# rfid_v1.net
KiCad netlist of a schematic drawn in EAGLE
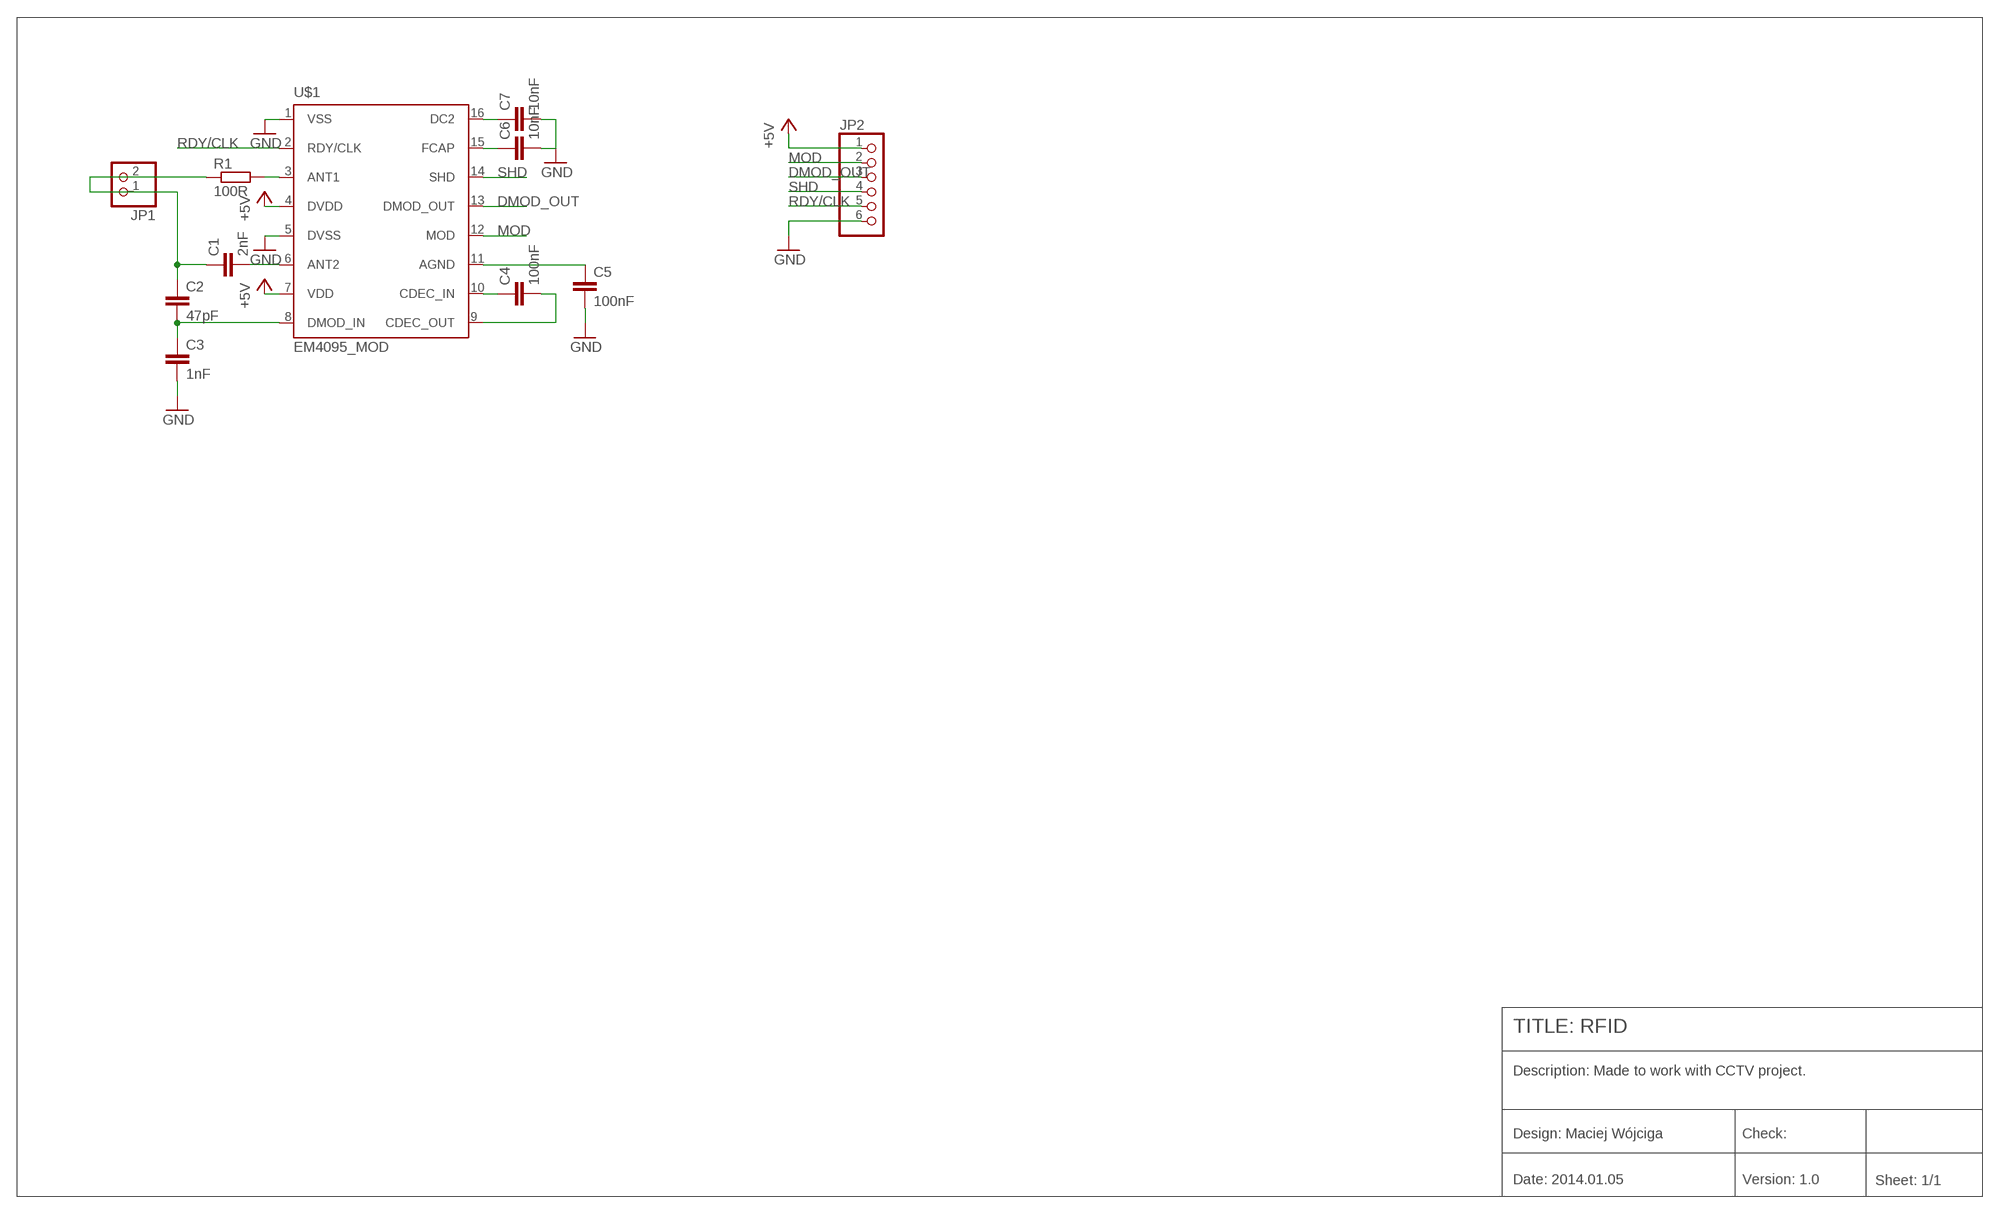
[diagram p0: schematic, sheet 1]

(export (version "E")
  (design (tool "Eeschema 10.0.6"))
  (components
    (comp (ref "C1")
      (value "2nF")
      (footprint "eagle-import:C025-024X044")
      (libsource (lib "eagle-import") (part "C-EU025-024X044"))
    )
    (comp (ref "C2")
      (value "47pF")
      (footprint "eagle-import:C025-024X044")
      (libsource (lib "eagle-import") (part "C-EU025-024X044"))
    )
    (comp (ref "C3")
      (value "1nF")
      (footprint "eagle-import:C025-024X044")
      (libsource (lib "eagle-import") (part "C-EU025-024X044"))
    )
    (comp (ref "C4")
      (value "100nF")
      (footprint "eagle-import:C025-024X044")
      (libsource (lib "eagle-import") (part "C-EU025-024X044"))
    )
    (comp (ref "C5")
      (value "100nF")
      (footprint "eagle-import:C025-024X044")
      (libsource (lib "eagle-import") (part "C-EU025-024X044"))
    )
    (comp (ref "C6")
      (value "10nF")
      (footprint "eagle-import:C025-024X044")
      (libsource (lib "eagle-import") (part "C-EU025-024X044"))
    )
    (comp (ref "C7")
      (value "10nF")
      (footprint "eagle-import:C025-024X044")
      (libsource (lib "eagle-import") (part "C-EU025-024X044"))
    )
    (comp (ref "JP1")
      (value "PINHD-1X2")
      (footprint "eagle-import:1X02")
      (libsource (lib "eagle-import") (part "PINHD-1X2"))
    )
    (comp (ref "JP2")
      (value "PINHD-1X6/90")
      (footprint "eagle-import:1X06_90")
      (libsource (lib "eagle-import") (part "PINHD-1X6/90"))
    )
    (comp (ref "R1")
      (value "100R")
      (footprint "eagle-import:0207_10")
      (libsource (lib "eagle-import") (part "R-EU_0207/10"))
    )
    (comp (ref "U$1")
      (value "EM4095_MOD")
      (footprint "eagle-import:SO16")
      (libsource (lib "eagle-import") (part "EM4095_MOD"))
    )
  )
  (nets
    (net (code "1") (name "+5V") (class "Default")
      (node (ref "JP2") (pin "1") (pinfunction "1_1") (pintype "passive"))
      (node (ref "U$1") (pin "4") (pinfunction "DVDD_4") (pintype "power_in"))
      (node (ref "U$1") (pin "7") (pinfunction "VDD_7") (pintype "power_in"))
    )
    (net (code "2") (name "/DMOD_OUT") (class "Default")
      (node (ref "JP2") (pin "3") (pinfunction "3_3") (pintype "passive"))
      (node (ref "U$1") (pin "13") (pinfunction "DMOD_OUT_13") (pintype "output"))
    )
    (net (code "3") (name "/MOD") (class "Default")
      (node (ref "JP2") (pin "2") (pinfunction "2_2") (pintype "passive"))
      (node (ref "U$1") (pin "12") (pinfunction "MOD_12") (pintype "input"))
    )
    (net (code "4") (name "/RDY{slash}CLK") (class "Default")
      (node (ref "JP2") (pin "5") (pinfunction "5_5") (pintype "passive"))
      (node (ref "U$1") (pin "2") (pinfunction "RDY/CLK_2") (pintype "output"))
    )
    (net (code "5") (name "/SHD") (class "Default")
      (node (ref "JP2") (pin "4") (pinfunction "4_4") (pintype "passive"))
      (node (ref "U$1") (pin "14") (pinfunction "SHD_14") (pintype "input"))
    )
    (net (code "6") (name "GND") (class "Default")
      (node (ref "C3") (pin "2") (pinfunction "2_2") (pintype "passive"))
      (node (ref "C5") (pin "2") (pinfunction "2_2") (pintype "passive"))
      (node (ref "C6") (pin "2") (pinfunction "2_2") (pintype "passive"))
      (node (ref "C7") (pin "2") (pinfunction "2_2") (pintype "passive"))
      (node (ref "JP2") (pin "6") (pinfunction "6_6") (pintype "passive"))
      (node (ref "U$1") (pin "1") (pinfunction "VSS_1") (pintype "power_in"))
      (node (ref "U$1") (pin "5") (pinfunction "DVSS_5") (pintype "power_in"))
    )
    (net (code "7") (name "Net-(C1-Pad1)") (class "Default")
      (node (ref "C1") (pin "1") (pinfunction "1_1") (pintype "passive"))
      (node (ref "C2") (pin "1") (pinfunction "1_1") (pintype "passive"))
      (node (ref "JP1") (pin "1") (pinfunction "1_1") (pintype "passive"))
      (node (ref "JP1") (pin "2") (pinfunction "2_2") (pintype "passive"))
      (node (ref "R1") (pin "1") (pinfunction "1_1") (pintype "passive"))
    )
    (net (code "8") (name "Net-(U$1-AGND)") (class "Default")
      (node (ref "C5") (pin "1") (pinfunction "1_1") (pintype "passive"))
      (node (ref "U$1") (pin "11") (pinfunction "AGND_11") (pintype "power_in"))
    )
    (net (code "9") (name "Net-(U$1-ANT1)") (class "Default")
      (node (ref "R1") (pin "2") (pinfunction "2_2") (pintype "passive"))
      (node (ref "U$1") (pin "3") (pinfunction "ANT1_3") (pintype "passive"))
    )
    (net (code "10") (name "Net-(U$1-ANT2)") (class "Default")
      (node (ref "C1") (pin "2") (pinfunction "2_2") (pintype "passive"))
      (node (ref "U$1") (pin "6") (pinfunction "ANT2_6") (pintype "passive"))
    )
    (net (code "11") (name "Net-(U$1-CDEC_IN)") (class "Default")
      (node (ref "C4") (pin "1") (pinfunction "1_1") (pintype "passive"))
      (node (ref "U$1") (pin "10") (pinfunction "CDEC_IN_10") (pintype "input"))
    )
    (net (code "12") (name "Net-(U$1-CDEC_OUT)") (class "Default")
      (node (ref "C4") (pin "2") (pinfunction "2_2") (pintype "passive"))
      (node (ref "U$1") (pin "9") (pinfunction "CDEC_OUT_9") (pintype "output"))
    )
    (net (code "13") (name "Net-(U$1-DC2)") (class "Default")
      (node (ref "C7") (pin "1") (pinfunction "1_1") (pintype "passive"))
      (node (ref "U$1") (pin "16") (pinfunction "DC2_16") (pintype "passive"))
    )
    (net (code "14") (name "Net-(U$1-DMOD_IN)") (class "Default")
      (node (ref "C2") (pin "2") (pinfunction "2_2") (pintype "passive"))
      (node (ref "C3") (pin "1") (pinfunction "1_1") (pintype "passive"))
      (node (ref "U$1") (pin "8") (pinfunction "DMOD_IN_8") (pintype "input"))
    )
    (net (code "15") (name "Net-(U$1-FCAP)") (class "Default")
      (node (ref "C6") (pin "1") (pinfunction "1_1") (pintype "passive"))
      (node (ref "U$1") (pin "15") (pinfunction "FCAP_15") (pintype "passive"))
    )
  )
)
